# ESP-07.net
KiCad netlist of a schematic drawn in EAGLE
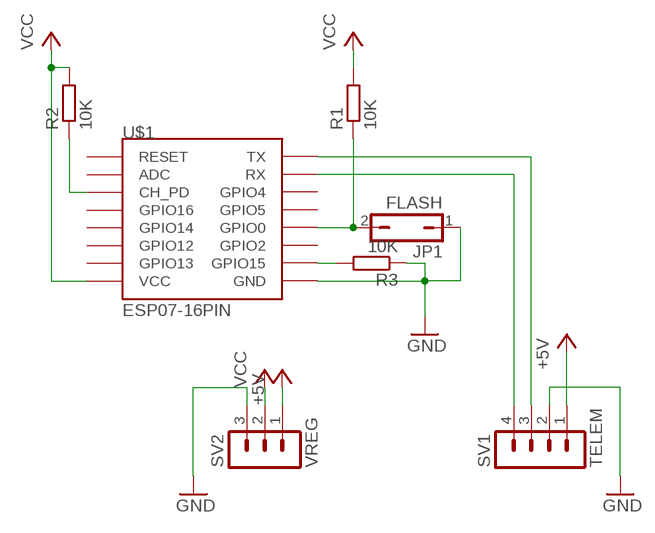
[diagram p0: schematic, sheet 1]

(export (version "E")
  (design (tool "Eeschema 10.0.6"))
  (components
    (comp (ref "JP1")
      (value "FLASH")
      (footprint "eagle-import:JP1")
      (libsource (lib "eagle-import") (part "JP1Q"))
    )
    (comp (ref "R1")
      (value "10K")
      (footprint "eagle-import:R0805")
      (libsource (lib "eagle-import") (part "R-EU_R0805"))
    )
    (comp (ref "R2")
      (value "10K")
      (footprint "eagle-import:R0805")
      (libsource (lib "eagle-import") (part "R-EU_R0805"))
    )
    (comp (ref "R3")
      (value "10K")
      (footprint "eagle-import:R0805")
      (libsource (lib "eagle-import") (part "R-EU_R0805"))
    )
    (comp (ref "SV1")
      (value "TELEM")
      (footprint "eagle-import:MA04-1")
      (libsource (lib "eagle-import") (part "MA04-1"))
    )
    (comp (ref "SV2")
      (value "VREG")
      (footprint "eagle-import:MA03-1")
      (libsource (lib "eagle-import") (part "MA03-1"))
    )
    (comp (ref "U$1")
      (value "ESP07-16PIN")
      (footprint "eagle-import:ESP07-16PIN")
      (libsource (lib "eagle-import") (part "ESP07-16PIN"))
    )
  )
  (nets
    (net (code "1") (name "+5V") (class "Default")
      (node (ref "SV1") (pin "1") (pinfunction "1_1") (pintype "passive"))
      (node (ref "SV2") (pin "1") (pinfunction "1_1") (pintype "passive"))
    )
    (net (code "2") (name "GND") (class "Default")
      (node (ref "JP1") (pin "1") (pinfunction "1_1") (pintype "passive"))
      (node (ref "R3") (pin "1") (pinfunction "1_1") (pintype "passive"))
      (node (ref "SV1") (pin "2") (pinfunction "2_2") (pintype "passive"))
      (node (ref "SV2") (pin "3") (pinfunction "3_3") (pintype "passive"))
      (node (ref "U$1") (pin "GND") (pinfunction "GND_GND") (pintype "bidirectional"))
    )
    (net (code "3") (name "Net-(JP1-Pad2)") (class "Default")
      (node (ref "JP1") (pin "2") (pinfunction "2_2") (pintype "passive"))
      (node (ref "R1") (pin "1") (pinfunction "1_1") (pintype "passive"))
      (node (ref "U$1") (pin "GPIO0") (pinfunction "GPIO0_GPIO0") (pintype "bidirectional"))
    )
    (net (code "4") (name "Net-(R2-Pad1)") (class "Default")
      (node (ref "R2") (pin "1") (pinfunction "1_1") (pintype "passive"))
      (node (ref "U$1") (pin "CH_PD") (pinfunction "CH_PD_CH_PD") (pintype "bidirectional"))
    )
    (net (code "5") (name "Net-(R3-Pad2)") (class "Default")
      (node (ref "R3") (pin "2") (pinfunction "2_2") (pintype "passive"))
      (node (ref "U$1") (pin "GPIO15") (pinfunction "GPIO15_GPIO15") (pintype "bidirectional"))
    )
    (net (code "6") (name "Net-(SV1-Pad3)") (class "Default")
      (node (ref "SV1") (pin "3") (pinfunction "3_3") (pintype "passive"))
      (node (ref "U$1") (pin "TX") (pinfunction "TX_TX") (pintype "bidirectional"))
    )
    (net (code "7") (name "Net-(SV1-Pad4)") (class "Default")
      (node (ref "SV1") (pin "4") (pinfunction "4_4") (pintype "passive"))
      (node (ref "U$1") (pin "RX") (pinfunction "RX_RX") (pintype "bidirectional"))
    )
    (net (code "8") (name "VCC") (class "Default")
      (node (ref "R1") (pin "2") (pinfunction "2_2") (pintype "passive"))
      (node (ref "R2") (pin "2") (pinfunction "2_2") (pintype "passive"))
      (node (ref "SV2") (pin "2") (pinfunction "2_2") (pintype "passive"))
      (node (ref "U$1") (pin "VCC") (pinfunction "VCC_VCC") (pintype "bidirectional"))
    )
    (net (code "9") (name "unconnected-(U$1-PadADC)") (class "Default")
      (node (ref "U$1") (pin "ADC") (pinfunction "ADC_ADC") (pintype "bidirectional"))
    )
    (net (code "10") (name "unconnected-(U$1-PadGPIO2)") (class "Default")
      (node (ref "U$1") (pin "GPIO2") (pinfunction "GPIO2_GPIO2") (pintype "bidirectional"))
    )
    (net (code "11") (name "unconnected-(U$1-PadGPIO4)") (class "Default")
      (node (ref "U$1") (pin "GPIO4") (pinfunction "GPIO4_GPIO4") (pintype "bidirectional"))
    )
    (net (code "12") (name "unconnected-(U$1-PadGPIO5)") (class "Default")
      (node (ref "U$1") (pin "GPIO5") (pinfunction "GPIO5_GPIO5") (pintype "bidirectional"))
    )
    (net (code "13") (name "unconnected-(U$1-PadGPIO12)") (class "Default")
      (node (ref "U$1") (pin "GPIO12") (pinfunction "GPIO12_GPIO12") (pintype "bidirectional"))
    )
    (net (code "14") (name "unconnected-(U$1-PadGPIO13)") (class "Default")
      (node (ref "U$1") (pin "GPIO13") (pinfunction "GPIO13_GPIO13") (pintype "bidirectional"))
    )
    (net (code "15") (name "unconnected-(U$1-PadGPIO14)") (class "Default")
      (node (ref "U$1") (pin "GPIO14") (pinfunction "GPIO14_GPIO14") (pintype "bidirectional"))
    )
    (net (code "16") (name "unconnected-(U$1-PadGPIO16)") (class "Default")
      (node (ref "U$1") (pin "GPIO16") (pinfunction "GPIO16_GPIO16") (pintype "bidirectional"))
    )
    (net (code "17") (name "unconnected-(U$1-RESET-PadREST)") (class "Default")
      (node (ref "U$1") (pin "REST") (pinfunction "RESET_REST") (pintype "bidirectional"))
    )
  )
)
